# Sheet1.net
KiCad netlist of a schematic drawn in Altium Designer
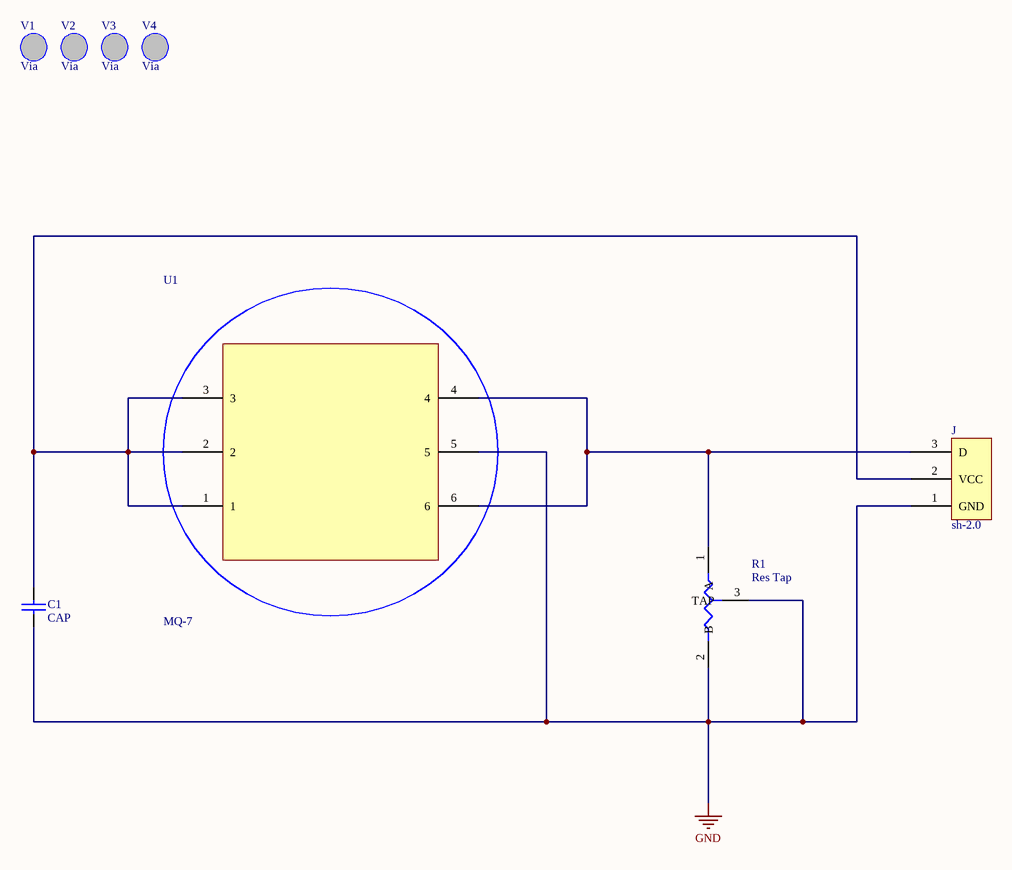
[diagram p0: Sheet1.SchDoc]

(export (version "E")
  (design (tool "Eeschema 10.0.6"))
  (components
    (comp (ref "C1")
      (value "CAP")
      (footprint "Miscellaneous Devices:1608[0603]")
      (libsource (lib "gupeng_sch") (part "CAP"))
    )
    (comp (ref "J") (value "sh-2.0") (footprint "sh-2.0") (libsource (lib "zhangchong") (part "sh-2.0")))
    (comp (ref "R1")
      (value "Res Tap")
      (footprint "BORUNS_3314J-1")
      (libsource (lib "gupeng_sch") (part "Res Tap"))
    )
    (comp (ref "U1")
      (value "MQ-7")
      (footprint "zhangchong:MQ-7")
      (libsource (lib "zhangchong") (part "MQ-7"))
    )
    (comp (ref "V1") (value "Via") (footprint "zhangchong:Via") (libsource (lib "zhangchong") (part "Via")))
    (comp (ref "V2") (value "Via") (footprint "zhangchong:Via") (libsource (lib "zhangchong") (part "Via")))
    (comp (ref "V3") (value "Via") (footprint "zhangchong:Via") (libsource (lib "zhangchong") (part "Via")))
    (comp (ref "V4") (value "Via") (footprint "zhangchong:Via") (libsource (lib "zhangchong") (part "Via")))
  )
  (nets
    (net (code "1") (name "GND") (class "Default")
      (node (ref "C1") (pin "2") (pinfunction "2_2") (pintype "passive"))
      (node (ref "J") (pin "1") (pinfunction "GND_1") (pintype "passive"))
      (node (ref "R1") (pin "2") (pinfunction "B_2") (pintype "passive"))
      (node (ref "R1") (pin "3") (pinfunction "TAP_3") (pintype "passive"))
      (node (ref "U1") (pin "5") (pinfunction "5_5") (pintype "passive"))
    )
    (net (code "2") (name "Net-(J-D)") (class "Default")
      (node (ref "J") (pin "3") (pinfunction "D_3") (pintype "passive"))
      (node (ref "R1") (pin "1") (pinfunction "A_1") (pintype "passive"))
      (node (ref "U1") (pin "4") (pinfunction "4_4") (pintype "passive"))
      (node (ref "U1") (pin "6") (pinfunction "6_6") (pintype "passive"))
    )
    (net (code "3") (name "Net-(J-VCC)") (class "Default")
      (node (ref "C1") (pin "1") (pinfunction "1_1") (pintype "passive"))
      (node (ref "J") (pin "2") (pinfunction "VCC_2") (pintype "passive"))
      (node (ref "U1") (pin "1") (pinfunction "1_1") (pintype "passive"))
      (node (ref "U1") (pin "2") (pinfunction "2_2") (pintype "passive"))
      (node (ref "U1") (pin "3") (pinfunction "3_3") (pintype "passive"))
    )
  )
)
